# IOB-Adapter-Output.net
KiCad netlist of a schematic drawn in EAGLE
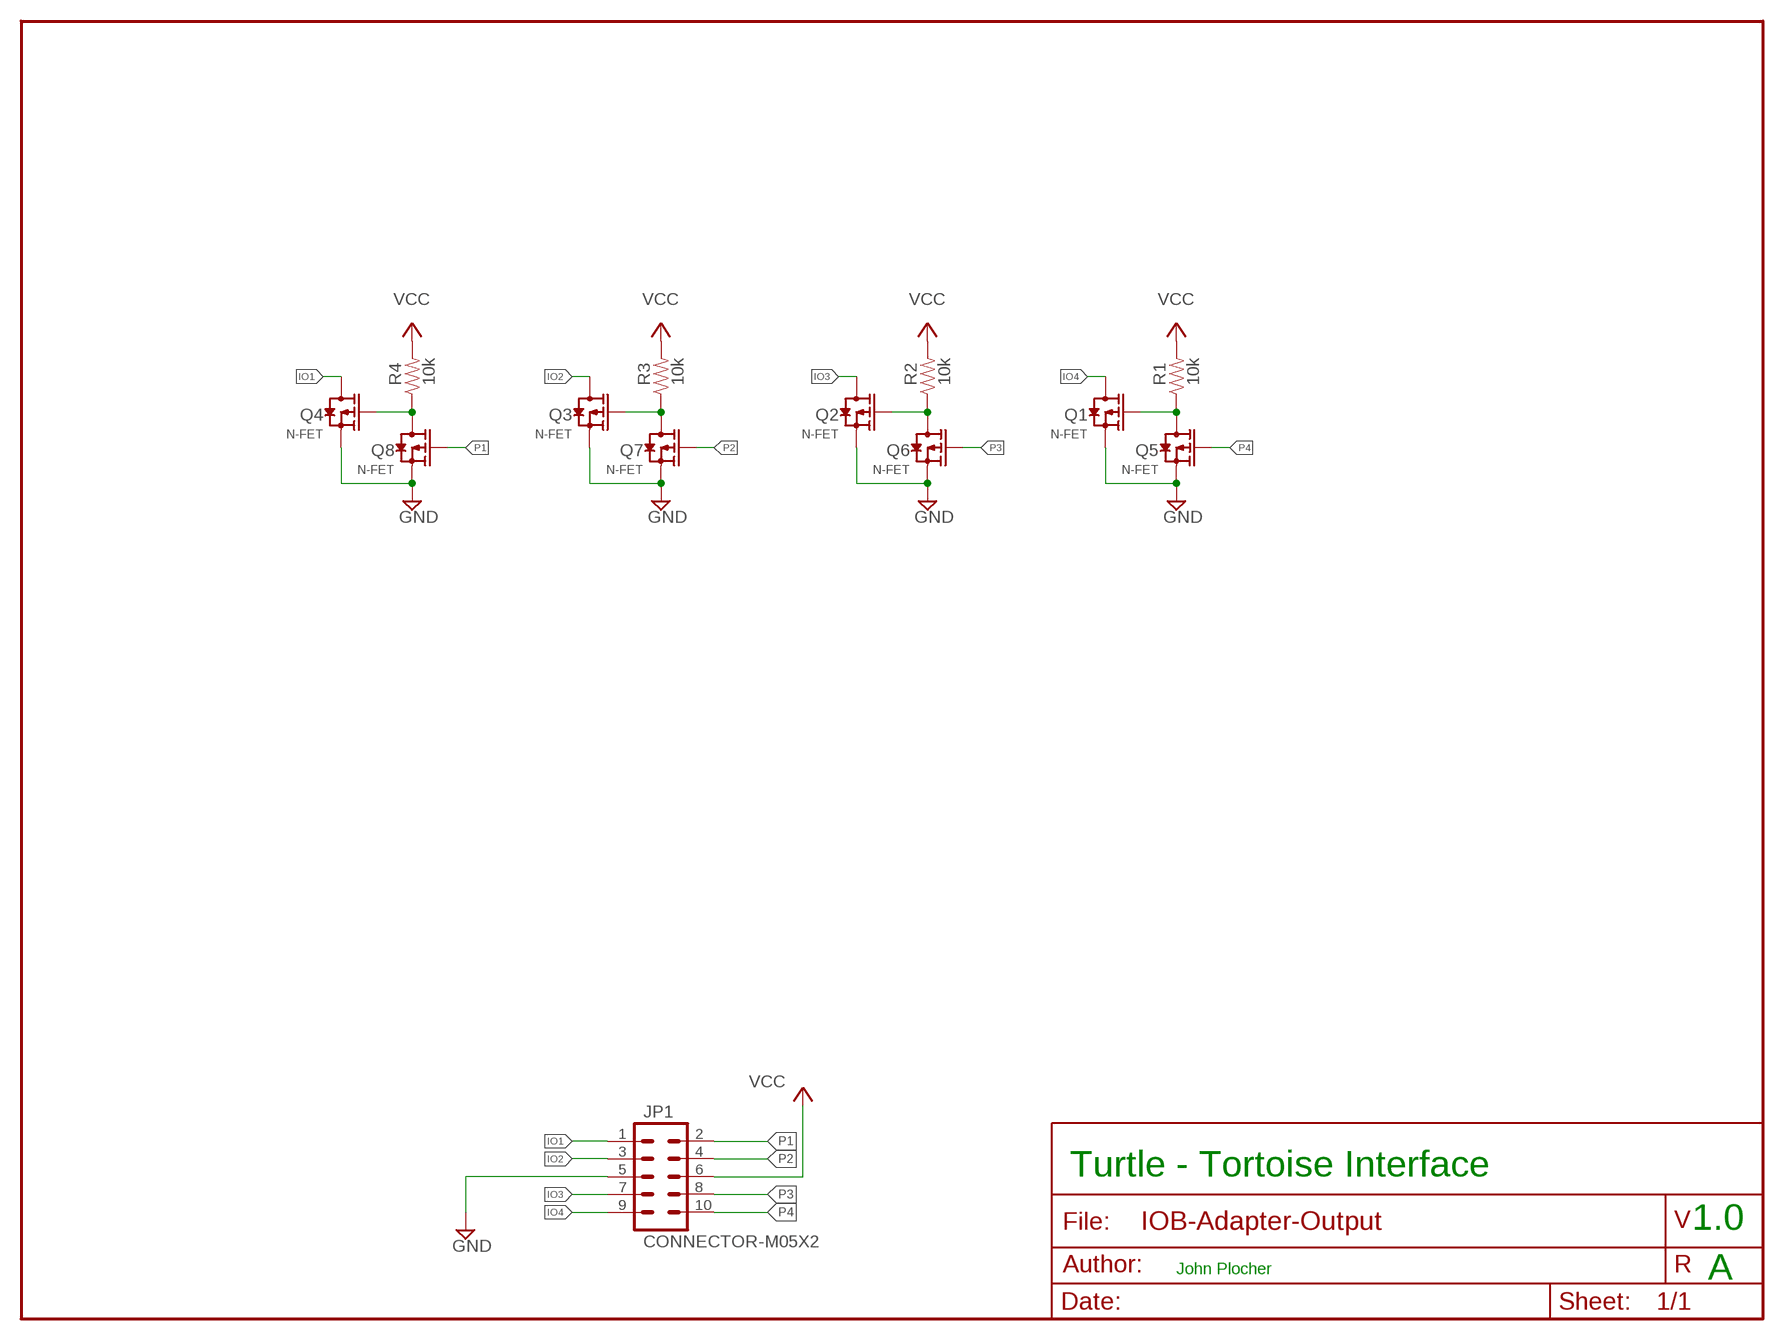
[diagram p0: schematic, sheet 1]

(export (version "E")
  (design (tool "Eeschema 10.0.6"))
  (components
    (comp (ref "JP1")
      (value "CONNECTOR-M05X2")
      (footprint "eagle-import:IOB-V3-MODULE")
      (libsource (lib "eagle-import") (part "CONNECTOR-M05X2"))
    )
    (comp (ref "Q1")
      (value "N-FET")
      (footprint "eagle-import:SOT23-3")
      (libsource (lib "eagle-import") (part "MOSFET-P"))
    )
    (comp (ref "Q2")
      (value "N-FET")
      (footprint "eagle-import:SOT23-3")
      (libsource (lib "eagle-import") (part "MOSFET-P"))
    )
    (comp (ref "Q3")
      (value "N-FET")
      (footprint "eagle-import:SOT23-3")
      (libsource (lib "eagle-import") (part "MOSFET-P"))
    )
    (comp (ref "Q4")
      (value "N-FET")
      (footprint "eagle-import:SOT23-3")
      (libsource (lib "eagle-import") (part "MOSFET-P"))
    )
    (comp (ref "Q5")
      (value "N-FET")
      (footprint "eagle-import:SOT23-3")
      (libsource (lib "eagle-import") (part "MOSFET-P"))
    )
    (comp (ref "Q6")
      (value "N-FET")
      (footprint "eagle-import:SOT23-3")
      (libsource (lib "eagle-import") (part "MOSFET-P"))
    )
    (comp (ref "Q7")
      (value "N-FET")
      (footprint "eagle-import:SOT23-3")
      (libsource (lib "eagle-import") (part "MOSFET-P"))
    )
    (comp (ref "Q8")
      (value "N-FET")
      (footprint "eagle-import:SOT23-3")
      (libsource (lib "eagle-import") (part "MOSFET-P"))
    )
    (comp (ref "R1")
      (value "10k")
      (footprint "eagle-import:0805-RES")
      (libsource (lib "eagle-import") (part "R0805-RES"))
    )
    (comp (ref "R2")
      (value "10k")
      (footprint "eagle-import:0805-RES")
      (libsource (lib "eagle-import") (part "R0805-RES"))
    )
    (comp (ref "R3")
      (value "10k")
      (footprint "eagle-import:0805-RES")
      (libsource (lib "eagle-import") (part "R0805-RES"))
    )
    (comp (ref "R4")
      (value "10k")
      (footprint "eagle-import:0805-RES")
      (libsource (lib "eagle-import") (part "R0805-RES"))
    )
  )
  (nets
    (net (code "1") (name "GND") (class "Default")
      (node (ref "JP1") (pin "5") (pinfunction "5_5") (pintype "passive"))
      (node (ref "Q1") (pin "2") (pinfunction "S_2") (pintype "passive"))
      (node (ref "Q2") (pin "2") (pinfunction "S_2") (pintype "passive"))
      (node (ref "Q3") (pin "2") (pinfunction "S_2") (pintype "passive"))
      (node (ref "Q4") (pin "2") (pinfunction "S_2") (pintype "passive"))
      (node (ref "Q5") (pin "2") (pinfunction "S_2") (pintype "passive"))
      (node (ref "Q6") (pin "2") (pinfunction "S_2") (pintype "passive"))
      (node (ref "Q7") (pin "2") (pinfunction "S_2") (pintype "passive"))
      (node (ref "Q8") (pin "2") (pinfunction "S_2") (pintype "passive"))
    )
    (net (code "2") (name "IO1") (class "Default")
      (node (ref "JP1") (pin "1") (pinfunction "1_1") (pintype "passive"))
      (node (ref "Q4") (pin "3") (pinfunction "D_3") (pintype "passive"))
    )
    (net (code "3") (name "IO2") (class "Default")
      (node (ref "JP1") (pin "3") (pinfunction "3_3") (pintype "passive"))
      (node (ref "Q3") (pin "3") (pinfunction "D_3") (pintype "passive"))
    )
    (net (code "4") (name "IO3") (class "Default")
      (node (ref "JP1") (pin "7") (pinfunction "7_7") (pintype "passive"))
      (node (ref "Q2") (pin "3") (pinfunction "D_3") (pintype "passive"))
    )
    (net (code "5") (name "IO4") (class "Default")
      (node (ref "JP1") (pin "9") (pinfunction "9_9") (pintype "passive"))
      (node (ref "Q1") (pin "3") (pinfunction "D_3") (pintype "passive"))
    )
    (net (code "6") (name "Net-(Q1-G)") (class "Default")
      (node (ref "Q1") (pin "1") (pinfunction "G_1") (pintype "passive"))
      (node (ref "Q5") (pin "3") (pinfunction "D_3") (pintype "passive"))
      (node (ref "R1") (pin "1") (pinfunction "1_1") (pintype "passive"))
    )
    (net (code "7") (name "Net-(Q2-G)") (class "Default")
      (node (ref "Q2") (pin "1") (pinfunction "G_1") (pintype "passive"))
      (node (ref "Q6") (pin "3") (pinfunction "D_3") (pintype "passive"))
      (node (ref "R2") (pin "1") (pinfunction "1_1") (pintype "passive"))
    )
    (net (code "8") (name "Net-(Q3-G)") (class "Default")
      (node (ref "Q3") (pin "1") (pinfunction "G_1") (pintype "passive"))
      (node (ref "Q7") (pin "3") (pinfunction "D_3") (pintype "passive"))
      (node (ref "R3") (pin "1") (pinfunction "1_1") (pintype "passive"))
    )
    (net (code "9") (name "Net-(Q4-G)") (class "Default")
      (node (ref "Q4") (pin "1") (pinfunction "G_1") (pintype "passive"))
      (node (ref "Q8") (pin "3") (pinfunction "D_3") (pintype "passive"))
      (node (ref "R4") (pin "1") (pinfunction "1_1") (pintype "passive"))
    )
    (net (code "10") (name "P1") (class "Default")
      (node (ref "JP1") (pin "2") (pinfunction "2_2") (pintype "passive"))
      (node (ref "Q8") (pin "1") (pinfunction "G_1") (pintype "passive"))
    )
    (net (code "11") (name "P2") (class "Default")
      (node (ref "JP1") (pin "4") (pinfunction "4_4") (pintype "passive"))
      (node (ref "Q7") (pin "1") (pinfunction "G_1") (pintype "passive"))
    )
    (net (code "12") (name "P3") (class "Default")
      (node (ref "JP1") (pin "8") (pinfunction "8_8") (pintype "passive"))
      (node (ref "Q6") (pin "1") (pinfunction "G_1") (pintype "passive"))
    )
    (net (code "13") (name "P4") (class "Default")
      (node (ref "JP1") (pin "10") (pinfunction "10_10") (pintype "passive"))
      (node (ref "Q5") (pin "1") (pinfunction "G_1") (pintype "passive"))
    )
    (net (code "14") (name "VCC") (class "Default")
      (node (ref "JP1") (pin "6") (pinfunction "6_6") (pintype "passive"))
      (node (ref "R1") (pin "2") (pinfunction "2_2") (pintype "passive"))
      (node (ref "R2") (pin "2") (pinfunction "2_2") (pintype "passive"))
      (node (ref "R3") (pin "2") (pinfunction "2_2") (pintype "passive"))
      (node (ref "R4") (pin "2") (pinfunction "2_2") (pintype "passive"))
    )
  )
)
